# RocketometerATMega.net
KiCad netlist of a schematic drawn in EAGLE
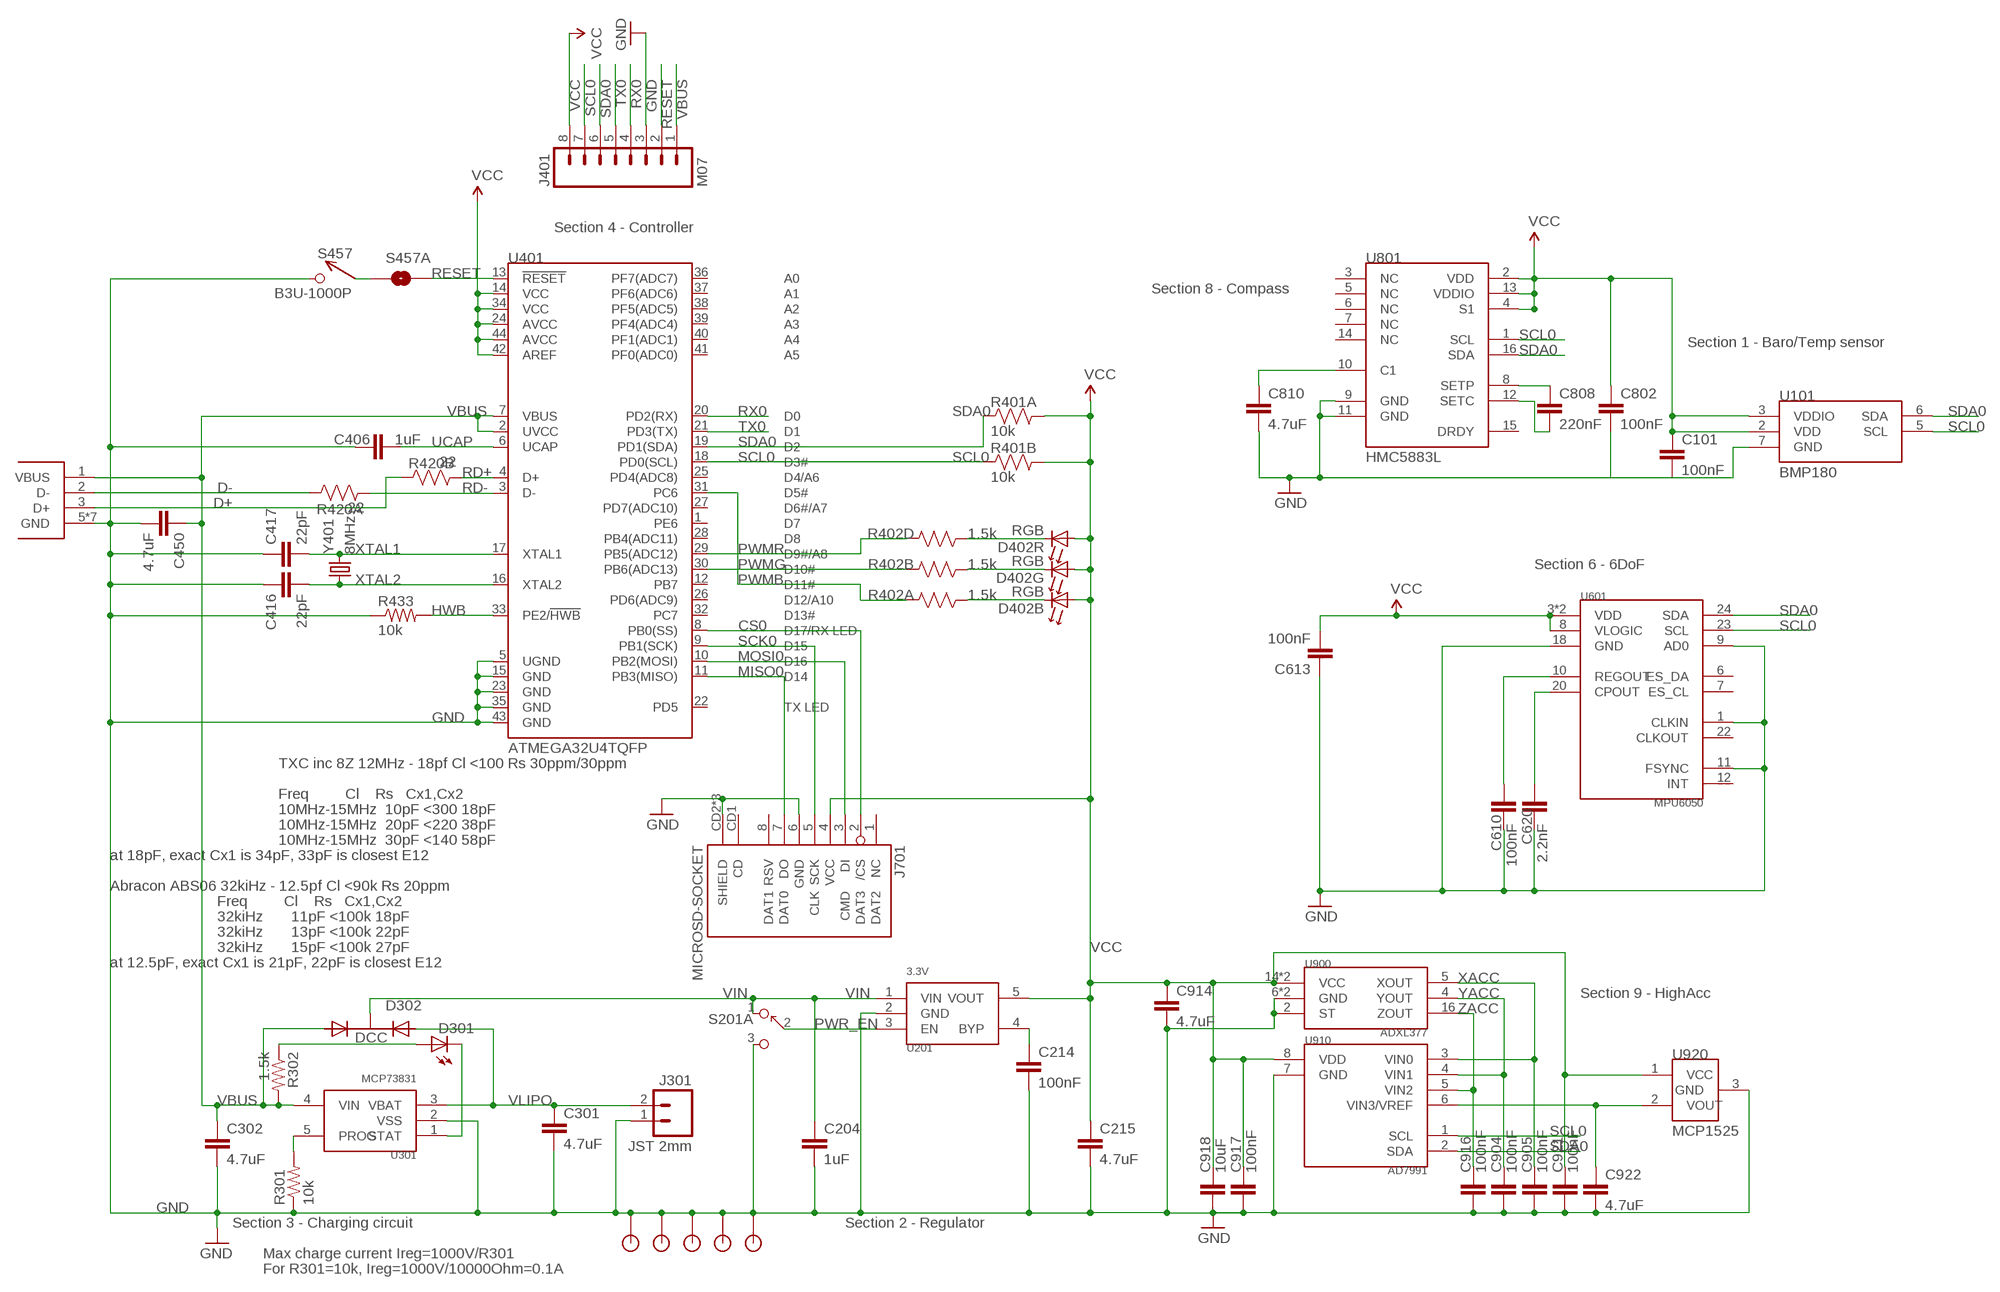
[diagram p0: schematic, sheet 1]

(export (version "E")
  (design (tool "Eeschema 10.0.6"))
  (components
    (comp (ref "C101")
      (value "100nF")
      (footprint "eagle-import:0402-CAP")
      (libsource (lib "eagle-import") (part "CAP0402-CAP"))
    )
    (comp (ref "C204")
      (value "1uF")
      (footprint "eagle-import:0402-CAP")
      (libsource (lib "eagle-import") (part "CAP0402-CAP"))
    )
    (comp (ref "C214")
      (value "100nF")
      (footprint "eagle-import:0402-CAP")
      (libsource (lib "eagle-import") (part "CAP0402-CAP"))
    )
    (comp (ref "C215")
      (value "4.7uF")
      (footprint "eagle-import:0402-CAP")
      (libsource (lib "eagle-import") (part "CAP0402-CAP"))
    )
    (comp (ref "C301")
      (value "4.7uF")
      (footprint "eagle-import:0402-CAP")
      (libsource (lib "eagle-import") (part "CAP0402-CAP"))
    )
    (comp (ref "C302")
      (value "4.7uF")
      (footprint "eagle-import:0402-CAP")
      (libsource (lib "eagle-import") (part "CAP0402-CAP"))
    )
    (comp (ref "C406")
      (value "1uF")
      (footprint "eagle-import:0402-CAP")
      (libsource (lib "eagle-import") (part "SparkFun-Passives_CAP0402-CAP"))
    )
    (comp (ref "C416")
      (value "22pF")
      (footprint "eagle-import:0402-CAP")
      (libsource (lib "eagle-import") (part "CAP0402-CAP"))
    )
    (comp (ref "C417")
      (value "22pF")
      (footprint "eagle-import:0402-CAP")
      (libsource (lib "eagle-import") (part "CAP0402-CAP"))
    )
    (comp (ref "C450")
      (value "4.7uF")
      (footprint "eagle-import:0402-CAP")
      (libsource (lib "eagle-import") (part "SparkFun-Passives_CAP0402-CAP"))
    )
    (comp (ref "C610")
      (value "100nF")
      (footprint "eagle-import:0402-CAP")
      (libsource (lib "eagle-import") (part "CAP0402-CAP"))
    )
    (comp (ref "C613")
      (value "100nF")
      (footprint "eagle-import:0402-CAP")
      (libsource (lib "eagle-import") (part "CAP0402-CAP"))
    )
    (comp (ref "C620")
      (value "2.2nF")
      (footprint "eagle-import:0402-CAP")
      (libsource (lib "eagle-import") (part "CAP0402-CAP"))
    )
    (comp (ref "C802")
      (value "100nF")
      (footprint "eagle-import:0402-CAP")
      (libsource (lib "eagle-import") (part "CAP0402-CAP"))
    )
    (comp (ref "C808")
      (value "220nF")
      (footprint "eagle-import:0402-CAP")
      (libsource (lib "eagle-import") (part "CAP0402-CAP"))
    )
    (comp (ref "C810")
      (value "4.7uF")
      (footprint "eagle-import:0402-CAP")
      (libsource (lib "eagle-import") (part "CAP0402-CAP"))
    )
    (comp (ref "C904")
      (value "100nF")
      (footprint "eagle-import:0402-CAP")
      (libsource (lib "eagle-import") (part "CAP0402-CAP"))
    )
    (comp (ref "C905")
      (value "100nF")
      (footprint "eagle-import:0402-CAP")
      (libsource (lib "eagle-import") (part "CAP0402-CAP"))
    )
    (comp (ref "C914")
      (value "4.7uF")
      (footprint "eagle-import:0402-CAP")
      (libsource (lib "eagle-import") (part "CAP0402-CAP"))
    )
    (comp (ref "C916")
      (value "100nF")
      (footprint "eagle-import:0402-CAP")
      (libsource (lib "eagle-import") (part "CAP0402-CAP"))
    )
    (comp (ref "C917")
      (value "100nF")
      (footprint "eagle-import:0402-CAP")
      (libsource (lib "eagle-import") (part "SparkFun-Passives_CAP0402-CAP"))
    )
    (comp (ref "C918")
      (value "10uF")
      (footprint "eagle-import:0603-CAP")
      (libsource (lib "eagle-import") (part "CAP0603-CAP"))
    )
    (comp (ref "C921")
      (value "100nF")
      (footprint "eagle-import:0402-CAP")
      (libsource (lib "eagle-import") (part "SparkFun-Passives_CAP0402-CAP"))
    )
    (comp (ref "C922")
      (value "4.7uF")
      (footprint "eagle-import:0402-CAP")
      (libsource (lib "eagle-import") (part "CAP0402-CAP"))
    )
    (comp (ref "D301")
      (value "YELLOW")
      (footprint "eagle-import:LED-0603")
      (libsource (lib "eagle-import") (part "LED0603"))
    )
    (comp (ref "D302")
      (value "DCC")
      (footprint "eagle-import:SOT-23-3")
      (libsource (lib "eagle-import") (part "PMEG2005CT"))
    )
    (comp (ref "D402")
      (value "RGB")
      (footprint "eagle-import:SMLP36")
      (fields (field (name "DIGIKEY") "846-1097-1-ND"))
      (libsource (lib "eagle-import") (part "SMLP36RGB2W(R)"))
    )
    (comp (ref "J301")
      (value "JST 2mm")
      (footprint "eagle-import:JST-2-SMD")
      (libsource (lib "eagle-import") (part "M02-JST-2MM-SMT"))
    )
    (comp (ref "J400")
      (value "USB_MICROB_JSTGCT")
      (footprint "eagle-import:USB_MICROB_3075")
      (libsource (lib "eagle-import") (part "USB_MICROB_JSTGCT"))
    )
    (comp (ref "J401")
      (value "M07")
      (footprint "eagle-import:1X08")
      (libsource (lib "eagle-import") (part "M081X08"))
    )
    (comp (ref "J701")
      (value "MICROSD-SOCKET")
      (footprint "eagle-import:MICROSD-SOCKET-PP")
      (libsource (lib "eagle-import") (part "MICROSD-SOCKET"))
    )
    (comp (ref "JP1")
      (value "STANDOFF")
      (footprint "eagle-import:STANDOFF")
      (libsource (lib "eagle-import") (part "STANDOFF"))
    )
    (comp (ref "JP2")
      (value "STANDOFF")
      (footprint "eagle-import:STANDOFF")
      (libsource (lib "eagle-import") (part "STANDOFF"))
    )
    (comp (ref "JP3")
      (value "STANDOFF")
      (footprint "eagle-import:STANDOFF")
      (libsource (lib "eagle-import") (part "STANDOFF"))
    )
    (comp (ref "JP4")
      (value "STANDOFF")
      (footprint "eagle-import:STANDOFF")
      (libsource (lib "eagle-import") (part "STANDOFF"))
    )
    (comp (ref "JP5")
      (value "STANDOFF")
      (footprint "eagle-import:STANDOFF")
      (libsource (lib "eagle-import") (part "STANDOFF"))
    )
    (comp (ref "R301")
      (value "10k")
      (footprint "eagle-import:0402-RES")
      (libsource (lib "eagle-import") (part "RESISTOR0402-RES"))
    )
    (comp (ref "R302")
      (value "1.5k")
      (footprint "eagle-import:0402-RES")
      (libsource (lib "eagle-import") (part "RESISTOR0402-RES"))
    )
    (comp (ref "R401")
      (value "10k")
      (footprint "eagle-import:CRA02")
      (fields (field (name "DIGIKEY") "Y5103CT-ND"))
      (libsource (lib "eagle-import") (part "RP2EXB24V"))
    )
    (comp (ref "R402")
      (value "1.5k")
      (footprint "eagle-import:CRA04")
      (fields (field (name "DIGIKEY") "CRA4S81.5KCT-ND"))
      (libsource (lib "eagle-import") (part "RP404"))
    )
    (comp (ref "R420")
      (value "22")
      (footprint "eagle-import:CRA02")
      (fields (field (name "DIGIKEY") "Y5220CT-ND"))
      (libsource (lib "eagle-import") (part "RP2EXB24V"))
    )
    (comp (ref "R433")
      (value "10k")
      (footprint "eagle-import:0402-RES")
      (libsource (lib "eagle-import") (part "SparkFun-Passives_RESISTOR0402-RES"))
    )
    (comp (ref "S201")
      (value "AYZ0202")
      (footprint "eagle-import:AYZ0202")
      (libsource (lib "eagle-import") (part "AYZ0202"))
    )
    (comp (ref "S457")
      (value "B3U-1000P")
      (footprint "eagle-import:B3U-1000P")
      (libsource (lib "eagle-import") (part "B3U-1000P"))
    )
    (comp (ref "S457A")
      (value "SOLDERJUMPERNO")
      (footprint "eagle-import:SJ_2S-NO")
      (libsource (lib "eagle-import") (part "SOLDERJUMPERNO"))
    )
    (comp (ref "U101")
      (value "BMP180")
      (footprint "eagle-import:BMP180")
      (libsource (lib "eagle-import") (part "BMP180"))
    )
    (comp (ref "U201")
      (value "3.3V")
      (footprint "eagle-import:SOT-23-5")
      (libsource (lib "eagle-import") (part "MIC5319D5"))
    )
    (comp (ref "U301")
      (value "MCP73831")
      (footprint "eagle-import:SOT-23-5")
      (libsource (lib "eagle-import") (part "MCP73831"))
    )
    (comp (ref "U401")
      (value "ATMEGA32U4TQFP")
      (footprint "eagle-import:SPARKFUN-DIGITALIC_TQFP44")
      (libsource (lib "eagle-import") (part "ATMEGA32U4TQFP"))
    )
    (comp (ref "U601")
      (value "MPU6050")
      (footprint "eagle-import:MPU60X0")
      (libsource (lib "eagle-import") (part "MPU6050"))
    )
    (comp (ref "U801")
      (value "HMC5883L")
      (footprint "eagle-import:16LPCC")
      (libsource (lib "eagle-import") (part "HMC5883LSMD"))
    )
    (comp (ref "U900")
      (value "ADXL377")
      (footprint "eagle-import:ADXL377")
      (libsource (lib "eagle-import") (part "ADXL377"))
    )
    (comp (ref "U910")
      (value "AD7991")
      (footprint "eagle-import:SOT-23-8")
      (libsource (lib "eagle-import") (part "AD799X"))
    )
    (comp (ref "U920")
      (value "MCP1525")
      (footprint "eagle-import:SOT-23-3")
      (libsource (lib "eagle-import") (part "MCP1525"))
    )
    (comp (ref "Y401")
      (value "8MHz")
      (footprint "eagle-import:CRYSTAL_SMD_3_2MM_2_5MM")
      (libsource (lib "eagle-import") (part "NX3225GD"))
    )
  )
  (nets
    (net (code "1") (name "/CS0") (class "Default")
      (node (ref "J701") (pin "2") (pinfunction "/CS_2") (pintype "bidirectional"))
      (node (ref "U401") (pin "8") (pinfunction "PB0(SS)_8") (pintype "bidirectional"))
    )
    (net (code "2") (name "/D+") (class "Default")
      (node (ref "J400") (pin "3") (pinfunction "D+_3") (pintype "bidirectional"))
      (node (ref "R420") (pin "2") (pinfunction "1_2") (pintype "passive"))
    )
    (net (code "3") (name "/D-") (class "Default")
      (node (ref "J400") (pin "2") (pinfunction "D-_2") (pintype "bidirectional"))
      (node (ref "R420") (pin "1") (pinfunction "1_1") (pintype "passive"))
    )
    (net (code "4") (name "/HWB") (class "Default")
      (node (ref "R433") (pin "2") (pinfunction "2_2") (pintype "passive"))
      (node (ref "U401") (pin "33") (pinfunction "PE2/~{HWB}_33") (pintype "bidirectional"))
    )
    (net (code "5") (name "/MISO0") (class "Default")
      (node (ref "J701") (pin "7") (pinfunction "DO_7") (pintype "bidirectional"))
      (node (ref "U401") (pin "11") (pinfunction "PB3(MISO)_11") (pintype "bidirectional"))
    )
    (net (code "6") (name "/MOSI0") (class "Default")
      (node (ref "J701") (pin "3") (pinfunction "DI_3") (pintype "bidirectional"))
      (node (ref "U401") (pin "10") (pinfunction "PB2(MOSI)_10") (pintype "bidirectional"))
    )
    (net (code "7") (name "/PWMB") (class "Default")
      (node (ref "R402") (pin "8") (pinfunction "2_8") (pintype "passive"))
      (node (ref "U401") (pin "31") (pinfunction "PC6_31") (pintype "bidirectional"))
    )
    (net (code "8") (name "/PWMG") (class "Default")
      (node (ref "R402") (pin "7") (pinfunction "2_7") (pintype "passive"))
      (node (ref "U401") (pin "30") (pinfunction "PB6(ADC13)_30") (pintype "bidirectional"))
    )
    (net (code "9") (name "/PWMR") (class "Default")
      (node (ref "R402") (pin "5") (pinfunction "2_5") (pintype "passive"))
      (node (ref "U401") (pin "29") (pinfunction "PB5(ADC12)_29") (pintype "bidirectional"))
    )
    (net (code "10") (name "/PWR_EN") (class "Default")
      (node (ref "S201") (pin "2") (pinfunction "P$3_2") (pintype "bidirectional"))
      (node (ref "U201") (pin "3") (pinfunction "EN_3") (pintype "bidirectional"))
    )
    (net (code "11") (name "/RD+") (class "Default")
      (node (ref "R420") (pin "3") (pinfunction "2_3") (pintype "passive"))
      (node (ref "U401") (pin "4") (pinfunction "D+_4") (pintype "bidirectional"))
    )
    (net (code "12") (name "/RD-") (class "Default")
      (node (ref "R420") (pin "4") (pinfunction "2_4") (pintype "passive"))
      (node (ref "U401") (pin "3") (pinfunction "D-_3") (pintype "bidirectional"))
    )
    (net (code "13") (name "/RESET") (class "Default")
      (node (ref "J401") (pin "2") (pinfunction "2_2") (pintype "passive"))
      (node (ref "S457A") (pin "2") (pinfunction "2_2") (pintype "passive"))
      (node (ref "U401") (pin "13") (pinfunction "~{RESET}_13") (pintype "bidirectional"))
    )
    (net (code "14") (name "/RX0") (class "Default")
      (node (ref "J401") (pin "4") (pinfunction "4_4") (pintype "passive"))
      (node (ref "U401") (pin "20") (pinfunction "PD2(RX)_20") (pintype "bidirectional"))
    )
    (net (code "15") (name "/SCK0") (class "Default")
      (node (ref "J701") (pin "5") (pinfunction "SCK_5") (pintype "bidirectional"))
      (node (ref "U401") (pin "9") (pinfunction "PB1(SCK)_9") (pintype "bidirectional"))
    )
    (net (code "16") (name "/SCL0") (class "Default")
      (node (ref "J401") (pin "7") (pinfunction "7_7") (pintype "passive"))
      (node (ref "R401") (pin "2") (pinfunction "1_2") (pintype "passive"))
      (node (ref "U101") (pin "5") (pinfunction "SCL_5") (pintype "input"))
      (node (ref "U401") (pin "18") (pinfunction "PD0(SCL)_18") (pintype "bidirectional"))
      (node (ref "U601") (pin "23") (pinfunction "SCL_23") (pintype "bidirectional"))
      (node (ref "U801") (pin "1") (pinfunction "SCL_1") (pintype "bidirectional"))
      (node (ref "U910") (pin "1") (pinfunction "SCL_1") (pintype "bidirectional"))
    )
    (net (code "17") (name "/SDA0") (class "Default")
      (node (ref "J401") (pin "6") (pinfunction "6_6") (pintype "passive"))
      (node (ref "R401") (pin "1") (pinfunction "1_1") (pintype "passive"))
      (node (ref "U101") (pin "6") (pinfunction "SDA_6") (pintype "bidirectional"))
      (node (ref "U401") (pin "19") (pinfunction "PD1(SDA)_19") (pintype "bidirectional"))
      (node (ref "U601") (pin "24") (pinfunction "SDA_24") (pintype "bidirectional"))
      (node (ref "U801") (pin "16") (pinfunction "SDA_16") (pintype "bidirectional"))
      (node (ref "U910") (pin "2") (pinfunction "SDA_2") (pintype "bidirectional"))
    )
    (net (code "18") (name "/TX0") (class "Default")
      (node (ref "J401") (pin "5") (pinfunction "5_5") (pintype "passive"))
      (node (ref "U401") (pin "21") (pinfunction "PD3(TX)_21") (pintype "bidirectional"))
    )
    (net (code "19") (name "/UCAP") (class "Default")
      (node (ref "C406") (pin "1") (pinfunction "1_1") (pintype "passive"))
      (node (ref "U401") (pin "6") (pinfunction "UCAP_6") (pintype "bidirectional"))
    )
    (net (code "20") (name "/VBUS") (class "Default")
      (node (ref "C302") (pin "1") (pinfunction "1_1") (pintype "passive"))
      (node (ref "C450") (pin "1") (pinfunction "1_1") (pintype "passive"))
      (node (ref "D302") (pin "1") (pinfunction "A1_1") (pintype "passive"))
      (node (ref "J400") (pin "1") (pinfunction "VBUS_1") (pintype "bidirectional"))
      (node (ref "J401") (pin "1") (pinfunction "1_1") (pintype "passive"))
      (node (ref "R302") (pin "2") (pinfunction "2_2") (pintype "passive"))
      (node (ref "U301") (pin "4") (pinfunction "VIN_4") (pintype "power_in"))
      (node (ref "U401") (pin "2") (pinfunction "UVCC_2") (pintype "bidirectional"))
      (node (ref "U401") (pin "7") (pinfunction "VBUS_7") (pintype "bidirectional"))
    )
    (net (code "21") (name "/VIN") (class "Default")
      (node (ref "C204") (pin "1") (pinfunction "1_1") (pintype "passive"))
      (node (ref "D302") (pin "3") (pinfunction "K_3") (pintype "passive"))
      (node (ref "S201") (pin "1") (pinfunction "P$1_1") (pintype "bidirectional"))
      (node (ref "U201") (pin "1") (pinfunction "VIN_1") (pintype "bidirectional"))
    )
    (net (code "22") (name "/VLIPO") (class "Default")
      (node (ref "C301") (pin "1") (pinfunction "1_1") (pintype "passive"))
      (node (ref "D302") (pin "2") (pinfunction "A2_2") (pintype "passive"))
      (node (ref "J301") (pin "2") (pinfunction "2_2") (pintype "passive"))
      (node (ref "U301") (pin "3") (pinfunction "VBAT_3") (pintype "power_in"))
    )
    (net (code "23") (name "/XACC") (class "Default")
      (node (ref "C905") (pin "1") (pinfunction "1_1") (pintype "passive"))
      (node (ref "U900") (pin "5") (pinfunction "XOUT_5") (pintype "bidirectional"))
      (node (ref "U910") (pin "3") (pinfunction "VIN0_3") (pintype "bidirectional"))
    )
    (net (code "24") (name "/XTAL1") (class "Default")
      (node (ref "C417") (pin "2") (pinfunction "2_2") (pintype "passive"))
      (node (ref "U401") (pin "17") (pinfunction "XTAL1_17") (pintype "bidirectional"))
      (node (ref "Y401") (pin "2") (pinfunction "2_2") (pintype "passive"))
    )
    (net (code "25") (name "/XTAL2") (class "Default")
      (node (ref "C416") (pin "2") (pinfunction "2_2") (pintype "passive"))
      (node (ref "U401") (pin "16") (pinfunction "XTAL2_16") (pintype "bidirectional"))
      (node (ref "Y401") (pin "1") (pinfunction "1_1") (pintype "passive"))
    )
    (net (code "26") (name "/YACC") (class "Default")
      (node (ref "C904") (pin "1") (pinfunction "1_1") (pintype "passive"))
      (node (ref "U900") (pin "4") (pinfunction "YOUT_4") (pintype "bidirectional"))
      (node (ref "U910") (pin "4") (pinfunction "VIN1_4") (pintype "bidirectional"))
    )
    (net (code "27") (name "/ZACC") (class "Default")
      (node (ref "C916") (pin "1") (pinfunction "1_1") (pintype "passive"))
      (node (ref "U900") (pin "16") (pinfunction "ZOUT_16") (pintype "bidirectional"))
      (node (ref "U910") (pin "5") (pinfunction "VIN2_5") (pintype "bidirectional"))
    )
    (net (code "28") (name "GND") (class "Default")
      (node (ref "C101") (pin "2") (pinfunction "2_2") (pintype "passive"))
      (node (ref "C204") (pin "2") (pinfunction "2_2") (pintype "passive"))
      (node (ref "C214") (pin "2") (pinfunction "2_2") (pintype "passive"))
      (node (ref "C215") (pin "2") (pinfunction "2_2") (pintype "passive"))
      (node (ref "C301") (pin "2") (pinfunction "2_2") (pintype "passive"))
      (node (ref "C302") (pin "2") (pinfunction "2_2") (pintype "passive"))
      (node (ref "C406") (pin "2") (pinfunction "2_2") (pintype "passive"))
      (node (ref "C416") (pin "1") (pinfunction "1_1") (pintype "passive"))
      (node (ref "C417") (pin "1") (pinfunction "1_1") (pintype "passive"))
      (node (ref "C450") (pin "2") (pinfunction "2_2") (pintype "passive"))
      (node (ref "C610") (pin "2") (pinfunction "2_2") (pintype "passive"))
      (node (ref "C613") (pin "1") (pinfunction "1_1") (pintype "passive"))
      (node (ref "C620") (pin "1") (pinfunction "1_1") (pintype "passive"))
      (node (ref "C802") (pin "2") (pinfunction "2_2") (pintype "passive"))
      (node (ref "C810") (pin "2") (pinfunction "2_2") (pintype "passive"))
      (node (ref "C904") (pin "2") (pinfunction "2_2") (pintype "passive"))
      (node (ref "C905") (pin "2") (pinfunction "2_2") (pintype "passive"))
      (node (ref "C914") (pin "2") (pinfunction "2_2") (pintype "passive"))
      (node (ref "C916") (pin "2") (pinfunction "2_2") (pintype "passive"))
      (node (ref "C917") (pin "2") (pinfunction "2_2") (pintype "passive"))
      (node (ref "C918") (pin "2") (pinfunction "2_2") (pintype "passive"))
      (node (ref "C921") (pin "2") (pinfunction "2_2") (pintype "passive"))
      (node (ref "C922") (pin "2") (pinfunction "2_2") (pintype "passive"))
      (node (ref "J301") (pin "1") (pinfunction "1_1") (pintype "passive"))
      (node (ref "J400") (pin "5") (pinfunction "GND_5") (pintype "bidirectional"))
      (node (ref "J400") (pin "P$1") (pinfunction "GND_P$1") (pintype "bidirectional"))
      (node (ref "J400") (pin "P$10") (pinfunction "GND_P$10") (pintype "bidirectional"))
      (node (ref "J400") (pin "P$2") (pinfunction "GND_P$2") (pintype "bidirectional"))
      (node (ref "J400") (pin "P$3") (pinfunction "GND_P$3") (pintype "bidirectional"))
      (node (ref "J400") (pin "P$4") (pinfunction "GND_P$4") (pintype "bidirectional"))
      (node (ref "J400") (pin "P$8") (pinfunction "GND_P$8") (pintype "bidirectional"))
      (node (ref "J401") (pin "3") (pinfunction "3_3") (pintype "passive"))
      (node (ref "J701") (pin "6") (pinfunction "GND_6") (pintype "bidirectional"))
      (node (ref "J701") (pin "CD2") (pinfunction "SHIELD_CD2") (pintype "bidirectional"))
      (node (ref "J701") (pin "GND1") (pinfunction "SHIELD_GND1") (pintype "bidirectional"))
      (node (ref "J701") (pin "GND3") (pinfunction "SHIELD_GND3") (pintype "bidirectional"))
      (node (ref "JP1") (pin "P$1") (pinfunction "P$1_P$1") (pintype "bidirectional"))
      (node (ref "JP2") (pin "P$1") (pinfunction "P$1_P$1") (pintype "bidirectional"))
      (node (ref "JP3") (pin "P$1") (pinfunction "P$1_P$1") (pintype "bidirectional"))
      (node (ref "JP4") (pin "P$1") (pinfunction "P$1_P$1") (pintype "bidirectional"))
      (node (ref "JP5") (pin "P$1") (pinfunction "P$1_P$1") (pintype "bidirectional"))
      (node (ref "R301") (pin "1") (pinfunction "1_1") (pintype "passive"))
      (node (ref "R433") (pin "1") (pinfunction "1_1") (pintype "passive"))
      (node (ref "S201") (pin "3") (pinfunction "P$2_3") (pintype "bidirectional"))
      (node (ref "S457") (pin "P$2") (pinfunction "2_P$2") (pintype "bidirectional"))
      (node (ref "U101") (pin "7") (pinfunction "GND_7") (pintype "power_in"))
      (node (ref "U201") (pin "2") (pinfunction "GND_2") (pintype "bidirectional"))
      (node (ref "U301") (pin "2") (pinfunction "VSS_2") (pintype "power_in"))
      (node (ref "U401") (pin "15") (pinfunction "GND_15") (pintype "bidirectional"))
      (node (ref "U401") (pin "23") (pinfunction "GND_23") (pintype "bidirectional"))
      (node (ref "U401") (pin "35") (pinfunction "GND_35") (pintype "bidirectional"))
      (node (ref "U401") (pin "43") (pinfunction "GND_43") (pintype "bidirectional"))
      (node (ref "U401") (pin "5") (pinfunction "UGND_5") (pintype "bidirectional"))
      (node (ref "U601") (pin "1") (pinfunction "CLKIN_1") (pintype "bidirectional"))
      (node (ref "U601") (pin "11") (pinfunction "FSYNC_11") (pintype "bidirectional"))
      (node (ref "U601") (pin "18") (pinfunction "GND_18") (pintype "bidirectional"))
      (node (ref "U601") (pin "9") (pinfunction "AD0_9") (pintype "bidirectional"))
      (node (ref "U801") (pin "11") (pinfunction "GND_11") (pintype "bidirectional"))
      (node (ref "U801") (pin "9") (pinfunction "GND_9") (pintype "bidirectional"))
      (node (ref "U900") (pin "2") (pinfunction "ST_2") (pintype "bidirectional"))
      (node (ref "U900") (pin "6") (pinfunction "GND_6") (pintype "bidirectional"))
      (node (ref "U900") (pin "7") (pinfunction "GND_7") (pintype "bidirectional"))
      (node (ref "U910") (pin "7") (pinfunction "GND_7") (pintype "bidirectional"))
      (node (ref "U920") (pin "3") (pinfunction "GND_3") (pintype "bidirectional"))
    )
    (net (code "29") (name "Net-(D301-PadA)") (class "Default")
      (node (ref "D301") (pin "A") (pinfunction "A_A") (pintype "passive"))
      (node (ref "R302") (pin "1") (pinfunction "1_1") (pintype "passive"))
    )
    (net (code "30") (name "Net-(D402A-C)") (class "Default")
      (node (ref "D402") (pin "1") (pinfunction "C_1") (pintype "passive"))
      (node (ref "R402") (pin "1") (pinfunction "1_1") (pintype "passive"))
    )
    (net (code "31") (name "Net-(D402B-C)") (class "Default")
      (node (ref "D402") (pin "3") (pinfunction "C_3") (pintype "passive"))
      (node (ref "R402") (pin "2") (pinfunction "1_2") (pintype "passive"))
    )
    (net (code "32") (name "Net-(D402C-C)") (class "Default")
      (node (ref "D402") (pin "5") (pinfunction "C_5") (pintype "passive"))
      (node (ref "R402") (pin "4") (pinfunction "1_4") (pintype "passive"))
    )
    (net (code "33") (name "Net-(S457-1)") (class "Default")
      (node (ref "S457") (pin "P$1") (pinfunction "1_P$1") (pintype "bidirectional"))
      (node (ref "S457A") (pin "1") (pinfunction "1_1") (pintype "passive"))
    )
    (net (code "34") (name "Net-(U201-BYP)") (class "Default")
      (node (ref "C214") (pin "1") (pinfunction "1_1") (pintype "passive"))
      (node (ref "U201") (pin "4") (pinfunction "BYP_4") (pintype "bidirectional"))
    )
    (net (code "35") (name "Net-(U301-PROG)") (class "Default")
      (node (ref "R301") (pin "2") (pinfunction "2_2") (pintype "passive"))
      (node (ref "U301") (pin "5") (pinfunction "PROG_5") (pintype "passive"))
    )
    (net (code "36") (name "Net-(U301-STAT)") (class "Default")
      (node (ref "D301") (pin "C") (pinfunction "C_C") (pintype "passive"))
      (node (ref "U301") (pin "1") (pinfunction "STAT_1") (pintype "bidirectional"))
    )
    (net (code "37") (name "Net-(U601-CPOUT)") (class "Default")
      (node (ref "C620") (pin "2") (pinfunction "2_2") (pintype "passive"))
      (node (ref "U601") (pin "20") (pinfunction "CPOUT_20") (pintype "bidirectional"))
    )
    (net (code "38") (name "Net-(U601-REGOUT)") (class "Default")
      (node (ref "C610") (pin "1") (pinfunction "1_1") (pintype "passive"))
      (node (ref "U601") (pin "10") (pinfunction "REGOUT_10") (pintype "bidirectional"))
    )
    (net (code "39") (name "Net-(U801-C1)") (class "Default")
      (node (ref "C810") (pin "1") (pinfunction "1_1") (pintype "passive"))
      (node (ref "U801") (pin "10") (pinfunction "C1_10") (pintype "bidirectional"))
    )
    (net (code "40") (name "Net-(U801-SETC)") (class "Default")
      (node (ref "C808") (pin "2") (pinfunction "2_2") (pintype "passive"))
      (node (ref "U801") (pin "12") (pinfunction "SETC_12") (pintype "bidirectional"))
    )
    (net (code "41") (name "Net-(U801-SETP)") (class "Default")
      (node (ref "C808") (pin "1") (pinfunction "1_1") (pintype "passive"))
      (node (ref "U801") (pin "8") (pinfunction "SETP_8") (pintype "bidirectional"))
    )
    (net (code "42") (name "Net-(U910-VIN3{slash}VREF)") (class "Default")
      (node (ref "C922") (pin "1") (pinfunction "1_1") (pintype "passive"))
      (node (ref "U910") (pin "6") (pinfunction "VIN3/VREF_6") (pintype "bidirectional"))
      (node (ref "U920") (pin "2") (pinfunction "VOUT_2") (pintype "bidirectional"))
    )
    (net (code "43") (name "VCC") (class "Default")
      (node (ref "C101") (pin "1") (pinfunction "1_1") (pintype "passive"))
      (node (ref "C215") (pin "1") (pinfunction "1_1") (pintype "passive"))
      (node (ref "C613") (pin "2") (pinfunction "2_2") (pintype "passive"))
      (node (ref "C802") (pin "1") (pinfunction "1_1") (pintype "passive"))
      (node (ref "C914") (pin "1") (pinfunction "1_1") (pintype "passive"))
      (node (ref "C917") (pin "1") (pinfunction "1_1") (pintype "passive"))
      (node (ref "C918") (pin "1") (pinfunction "1_1") (pintype "passive"))
      (node (ref "C921") (pin "1") (pinfunction "1_1") (pintype "passive"))
      (node (ref "D402") (pin "2") (pinfunction "A_2") (pintype "passive"))
      (node (ref "D402") (pin "4") (pinfunction "A_4") (pintype "passive"))
      (node (ref "D402") (pin "6") (pinfunction "A_6") (pintype "passive"))
      (node (ref "J401") (pin "8") (pinfunction "8_8") (pintype "passive"))
      (node (ref "J701") (pin "4") (pinfunction "VCC_4") (pintype "bidirectional"))
      (node (ref "R401") (pin "3") (pinfunction "2_3") (pintype "passive"))
      (node (ref "R401") (pin "4") (pinfunction "2_4") (pintype "passive"))
      (node (ref "U101") (pin "2") (pinfunction "VDD_2") (pintype "power_in"))
      (node (ref "U101") (pin "3") (pinfunction "VDDIO_3") (pintype "power_in"))
      (node (ref "U201") (pin "5") (pinfunction "VOUT_5") (pintype "bidirectional"))
      (node (ref "U401") (pin "14") (pinfunction "VCC_14") (pintype "bidirectional"))
      (node (ref "U401") (pin "24") (pinfunction "AVCC_24") (pintype "bidirectional"))
      (node (ref "U401") (pin "34") (pinfunction "VCC_34") (pintype "bidirectional"))
      (node (ref "U401") (pin "42") (pinfunction "AREF_42") (pintype "bidirectional"))
      (node (ref "U401") (pin "44") (pinfunction "AVCC_44") (pintype "bidirectional"))
      (node (ref "U601") (pin "13") (pinfunction "VDD_13") (pintype "bidirectional"))
      (node (ref "U601") (pin "3") (pinfunction "VDD_3") (pintype "bidirectional"))
      (node (ref "U601") (pin "8") (pinfunction "VLOGIC_8") (pintype "bidirectional"))
      (node (ref "U801") (pin "13") (pinfunction "VDDIO_13") (pintype "bidirectional"))
      (node (ref "U801") (pin "2") (pinfunction "VDD_2") (pintype "bidirectional"))
      (node (ref "U801") (pin "4") (pinfunction "S1_4") (pintype "bidirectional"))
      (node (ref "U900") (pin "14") (pinfunction "VCC_14") (pintype "bidirectional"))
      (node (ref "U900") (pin "15") (pinfunction "VCC_15") (pintype "bidirectional"))
      (node (ref "U910") (pin "8") (pinfunction "VDD_8") (pintype "bidirectional"))
      (node (ref "U920") (pin "1") (pinfunction "VCC_1") (pintype "bidirectional"))
    )
    (net (code "44") (name "unconnected-(J701-CD-PadCD1)") (class "Default")
      (node (ref "J701") (pin "CD1") (pinfunction "CD_CD1") (pintype "bidirectional"))
    )
    (net (code "45") (name "unconnected-(J701-NC-Pad1)") (class "Default")
      (node (ref "J701") (pin "1") (pinfunction "NC_1") (pintype "bidirectional"))
    )
    (net (code "46") (name "unconnected-(J701-RSV-Pad8)") (class "Default")
      (node (ref "J701") (pin "8") (pinfunction "RSV_8") (pintype "bidirectional"))
    )
    (net (code "47") (name "unconnected-(U401-PB4(ADC11)-Pad28)") (class "Default")
      (node (ref "U401") (pin "28") (pinfunction "PB4(ADC11)_28") (pintype "bidirectional"))
    )
    (net (code "48") (name "unconnected-(U401-PB7-Pad12)") (class "Default")
      (node (ref "U401") (pin "12") (pinfunction "PB7_12") (pintype "bidirectional"))
    )
    (net (code "49") (name "unconnected-(U401-PC7-Pad32)") (class "Default")
      (node (ref "U401") (pin "32") (pinfunction "PC7_32") (pintype "bidirectional"))
    )
    (net (code "50") (name "unconnected-(U401-PD4(ADC8)-Pad25)") (class "Default")
      (node (ref "U401") (pin "25") (pinfunction "PD4(ADC8)_25") (pintype "bidirectional"))
    )
    (net (code "51") (name "unconnected-(U401-PD5-Pad22)") (class "Default")
      (node (ref "U401") (pin "22") (pinfunction "PD5_22") (pintype "bidirectional"))
    )
    (net (code "52") (name "unconnected-(U401-PD6(ADC9)-Pad26)") (class "Default")
      (node (ref "U401") (pin "26") (pinfunction "PD6(ADC9)_26") (pintype "bidirectional"))
    )
    (net (code "53") (name "unconnected-(U401-PD7(ADC10)-Pad27)") (class "Default")
      (node (ref "U401") (pin "27") (pinfunction "PD7(ADC10)_27") (pintype "bidirectional"))
    )
    (net (code "54") (name "unconnected-(U401-PE6-Pad1)") (class "Default")
      (node (ref "U401") (pin "1") (pinfunction "PE6_1") (pintype "bidirectional"))
    )
    (net (code "55") (name "unconnected-(U401-PF0(ADC0)-Pad41)") (class "Default")
      (node (ref "U401") (pin "41") (pinfunction "PF0(ADC0)_41") (pintype "bidirectional"))
    )
    (net (code "56") (name "unconnected-(U401-PF1(ADC1)-Pad40)") (class "Default")
      (node (ref "U401") (pin "40") (pinfunction "PF1(ADC1)_40") (pintype "bidirectional"))
    )
    (net (code "57") (name "unconnected-(U401-PF4(ADC4)-Pad39)") (class "Default")
      (node (ref "U401") (pin "39") (pinfunction "PF4(ADC4)_39") (pintype "bidirectional"))
    )
    (net (code "58") (name "unconnected-(U401-PF5(ADC5)-Pad38)") (class "Default")
      (node (ref "U401") (pin "38") (pinfunction "PF5(ADC5)_38") (pintype "bidirectional"))
    )
    (net (code "59") (name "unconnected-(U401-PF6(ADC6)-Pad37)") (class "Default")
      (node (ref "U401") (pin "37") (pinfunction "PF6(ADC6)_37") (pintype "bidirectional"))
    )
    (net (code "60") (name "unconnected-(U401-PF7(ADC7)-Pad36)") (class "Default")
      (node (ref "U401") (pin "36") (pinfunction "PF7(ADC7)_36") (pintype "bidirectional"))
    )
    (net (code "61") (name "unconnected-(U601-CLKOUT-Pad22)") (class "Default")
      (node (ref "U601") (pin "22") (pinfunction "CLKOUT_22") (pintype "bidirectional"))
    )
    (net (code "62") (name "unconnected-(U601-ES_CL-Pad7)") (class "Default")
      (node (ref "U601") (pin "7") (pinfunction "ES_CL_7") (pintype "bidirectional"))
    )
    (net (code "63") (name "unconnected-(U601-ES_DA-Pad6)") (class "Default")
      (node (ref "U601") (pin "6") (pinfunction "ES_DA_6") (pintype "bidirectional"))
    )
    (net (code "64") (name "unconnected-(U601-INT-Pad12)") (class "Default")
      (node (ref "U601") (pin "12") (pinfunction "INT_12") (pintype "bidirectional"))
    )
    (net (code "65") (name "unconnected-(U801-DRDY-Pad15)") (class "Default")
      (node (ref "U801") (pin "15") (pinfunction "DRDY_15") (pintype "bidirectional"))
    )
    (net (code "66") (name "unconnected-(U801-NC-Pad3)") (class "Default")
      (node (ref "U801") (pin "3") (pinfunction "NC_3") (pintype "bidirectional"))
    )
    (net (code "67") (name "unconnected-(U801-NC-Pad5)") (class "Default")
      (node (ref "U801") (pin "5") (pinfunction "NC_5") (pintype "bidirectional"))
    )
    (net (code "68") (name "unconnected-(U801-NC-Pad6)") (class "Default")
      (node (ref "U801") (pin "6") (pinfunction "NC_6") (pintype "bidirectional"))
    )
    (net (code "69") (name "unconnected-(U801-NC-Pad7)") (class "Default")
      (node (ref "U801") (pin "7") (pinfunction "NC_7") (pintype "bidirectional"))
    )
    (net (code "70") (name "unconnected-(U801-NC-Pad14)") (class "Default")
      (node (ref "U801") (pin "14") (pinfunction "NC_14") (pintype "bidirectional"))
    )
  )
)
